# Schematics_-_Remote_Monitoring_Hardware.net
KiCad netlist of a schematic drawn in EAGLE
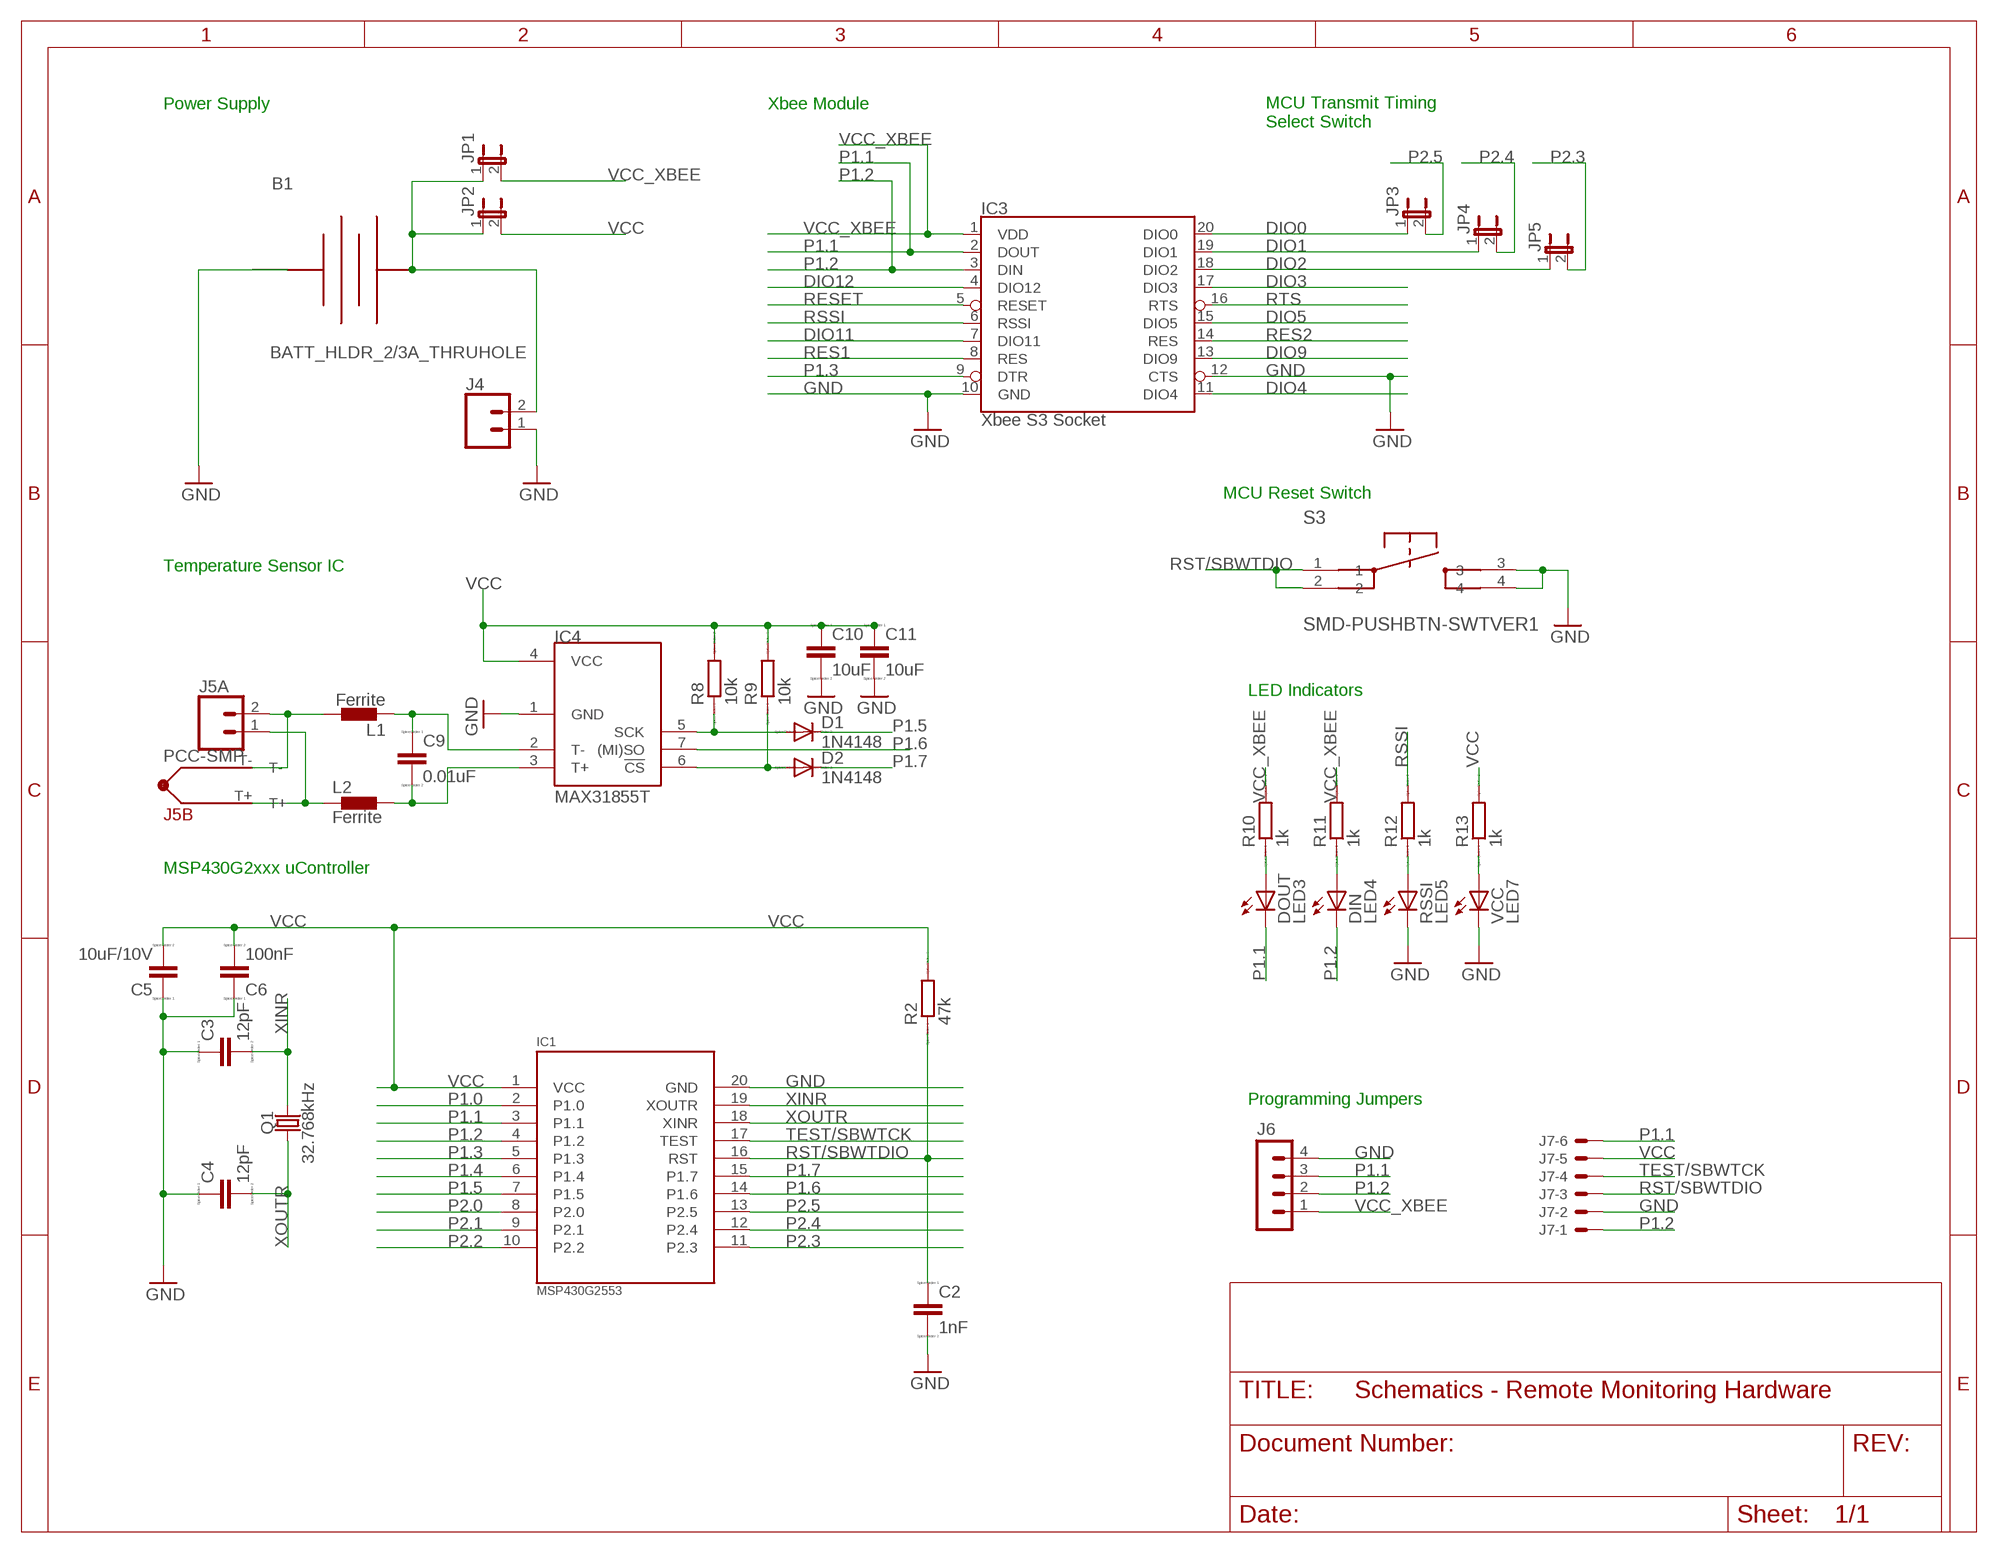
[diagram p0: schematic, sheet 1]

(export (version "E")
  (design (tool "Eeschema 10.0.6"))
  (components
    (comp (ref "B1")
      (value "BATT_HLDR_2/3A_THRUHOLE")
      (footprint "eagle-import:BATT_HLDR_2_3A_THRUHOLE")
      (libsource (lib "eagle-import") (part "BATT_HLDR_2/3A_THRUHOLE"))
    )
    (comp (ref "C2")
      (value "1nF")
      (footprint "eagle-import:C0805")
      (libsource (lib "eagle-import") (part "C"))
    )
    (comp (ref "C3")
      (value "12pF")
      (footprint "eagle-import:C0805")
      (libsource (lib "eagle-import") (part "C"))
    )
    (comp (ref "C4")
      (value "12pF")
      (footprint "eagle-import:C0805")
      (libsource (lib "eagle-import") (part "C"))
    )
    (comp (ref "C5")
      (value "10uF/10V")
      (footprint "eagle-import:C0805")
      (libsource (lib "eagle-import") (part "C"))
    )
    (comp (ref "C6")
      (value "100nF")
      (footprint "eagle-import:C0805")
      (libsource (lib "eagle-import") (part "C"))
    )
    (comp (ref "C9")
      (value "0.01uF")
      (footprint "eagle-import:C0805")
      (libsource (lib "eagle-import") (part "C"))
    )
    (comp (ref "C10")
      (value "10uF")
      (footprint "eagle-import:C0805")
      (libsource (lib "eagle-import") (part "C"))
    )
    (comp (ref "C11")
      (value "10uF")
      (footprint "eagle-import:C0805")
      (libsource (lib "eagle-import") (part "C"))
    )
    (comp (ref "D1")
      (value "1N4148")
      (footprint "eagle-import:SOD323-R")
      (libsource (lib "eagle-import") (part "DIODE-SOD323-R"))
    )
    (comp (ref "D2")
      (value "1N4148")
      (footprint "eagle-import:SOD323-R")
      (libsource (lib "eagle-import") (part "DIODE-SOD323-R"))
    )
    (comp (ref "DIN")
      (value "LED4")
      (footprint "eagle-import:SML0805")
      (libsource (lib "eagle-import") (part "LEDSML0805"))
    )
    (comp (ref "DOUT")
      (value "LED3")
      (footprint "eagle-import:SML0805")
      (libsource (lib "eagle-import") (part "LEDSML0805"))
    )
    (comp (ref "IC1")
      (value "MSP430G2553")
      (footprint "eagle-import:MSP430G2553IPW20")
      (libsource (lib "eagle-import") (part "MSP430G2553IPW20VER2TSSOP-20"))
    )
    (comp (ref "IC3")
      (value "Xbee S3 Socket")
      (footprint "eagle-import:XBEE-LONGPAD")
      (libsource (lib "eagle-import") (part "XBEELONGPAD"))
    )
    (comp (ref "IC4")
      (value "MAX31855T")
      (footprint "eagle-import:SOIC8")
      (libsource (lib "eagle-import") (part "MAX6675"))
    )
    (comp (ref "J4")
      (value "CONN_023.5MM")
      (footprint "eagle-import:SCREWTERMINAL-3.5MM-2")
      (libsource (lib "eagle-import") (part "CONN_023.5MM"))
    )
    (comp (ref "J5A")
      (value "CONN_023.5MM")
      (footprint "eagle-import:SCREWTERMINAL-3.5MM-2")
      (libsource (lib "eagle-import") (part "CONN_023.5MM"))
    )
    (comp (ref "J5B")
      (value "PCC-SMP")
      (footprint "eagle-import:PCC-SMP")
      (libsource (lib "eagle-import") (part "PCC-SMP"))
    )
    (comp (ref "J6")
      (value "MA04-1")
      (footprint "eagle-import:MA04-1")
      (libsource (lib "eagle-import") (part "MA04-1"))
    )
    (comp (ref "J7")
      (value "53047-06")
      (footprint "eagle-import:53047-06")
      (fields (field (name "MPN") "53047-0610-C"))
      (libsource (lib "eagle-import") (part "53?-06047"))
    )
    (comp (ref "JP1")
      (value "JUMPER-2PTH")
      (footprint "eagle-import:1X02")
      (libsource (lib "eagle-import") (part "JUMPER-2PTH"))
    )
    (comp (ref "JP2")
      (value "JUMPER-2PTH")
      (footprint "eagle-import:1X02")
      (libsource (lib "eagle-import") (part "JUMPER-2PTH"))
    )
    (comp (ref "JP3")
      (value "JUMPER-2PTH")
      (footprint "eagle-import:1X02")
      (libsource (lib "eagle-import") (part "JUMPER-2PTH"))
    )
    (comp (ref "JP4")
      (value "JUMPER-2PTH")
      (footprint "eagle-import:1X02")
      (libsource (lib "eagle-import") (part "JUMPER-2PTH"))
    )
    (comp (ref "JP5")
      (value "JUMPER-2PTH")
      (footprint "eagle-import:1X02")
      (libsource (lib "eagle-import") (part "JUMPER-2PTH"))
    )
    (comp (ref "L1")
      (value "Ferrite")
      (footprint "eagle-import:0402")
      (libsource (lib "eagle-import") (part "BLM15HB121SN1"))
    )
    (comp (ref "L2")
      (value "Ferrite")
      (footprint "eagle-import:0402")
      (libsource (lib "eagle-import") (part "BLM15HB121SN1"))
    )
    (comp (ref "Q1")
      (value "32.768kHz")
      (footprint "eagle-import:CRYSTAL-SMD-2X6-CYL")
      (libsource (lib "eagle-import") (part "CRYSTAL-32.768KHZSMD-2X6"))
    )
    (comp (ref "R2")
      (value "47k")
      (footprint "eagle-import:R0805")
      (libsource (lib "eagle-import") (part "R"))
    )
    (comp (ref "R8")
      (value "10k")
      (footprint "eagle-import:R0805")
      (libsource (lib "eagle-import") (part "R"))
    )
    (comp (ref "R9")
      (value "10k")
      (footprint "eagle-import:R0805")
      (libsource (lib "eagle-import") (part "R"))
    )
    (comp (ref "R10")
      (value "1k")
      (footprint "eagle-import:R0805")
      (libsource (lib "eagle-import") (part "R"))
    )
    (comp (ref "R11")
      (value "1k")
      (footprint "eagle-import:R0805")
      (libsource (lib "eagle-import") (part "R"))
    )
    (comp (ref "R12")
      (value "1k")
      (footprint "eagle-import:R0805")
      (libsource (lib "eagle-import") (part "R"))
    )
    (comp (ref "R13")
      (value "1k")
      (footprint "eagle-import:R0805")
      (libsource (lib "eagle-import") (part "R"))
    )
    (comp (ref "RSSI")
      (value "LED5")
      (footprint "eagle-import:SML0805")
      (libsource (lib "eagle-import") (part "LEDSML0805"))
    )
    (comp (ref "S3")
      (value "SMD-PUSHBTN-SWTVER1")
      (footprint "eagle-import:KPT-1187B")
      (libsource (lib "eagle-import") (part "SMD-PUSHBTN-SWTVER1"))
    )
    (comp (ref "VCC")
      (value "LED7")
      (footprint "eagle-import:SML0805")
      (libsource (lib "eagle-import") (part "LEDSML0805"))
    )
  )
  (nets
    (net (code "1") (name "/DIO0") (class "Default")
      (node (ref "IC3") (pin "20") (pinfunction "DIO0_20") (pintype "bidirectional"))
      (node (ref "JP3") (pin "1") (pinfunction "1_1") (pintype "passive"))
    )
    (net (code "2") (name "/DIO1") (class "Default")
      (node (ref "IC3") (pin "19") (pinfunction "DIO1_19") (pintype "bidirectional"))
      (node (ref "JP4") (pin "1") (pinfunction "1_1") (pintype "passive"))
    )
    (net (code "3") (name "/DIO2") (class "Default")
      (node (ref "IC3") (pin "18") (pinfunction "DIO2_18") (pintype "bidirectional"))
      (node (ref "JP5") (pin "1") (pinfunction "1_1") (pintype "passive"))
    )
    (net (code "4") (name "/DIO3") (class "Default")
      (node (ref "IC3") (pin "17") (pinfunction "DIO3_17") (pintype "bidirectional"))
    )
    (net (code "5") (name "/DIO4") (class "Default")
      (node (ref "IC3") (pin "11") (pinfunction "DIO4_11") (pintype "bidirectional"))
    )
    (net (code "6") (name "/DIO5") (class "Default")
      (node (ref "IC3") (pin "15") (pinfunction "DIO5_15") (pintype "bidirectional"))
    )
    (net (code "7") (name "/DIO9") (class "Default")
      (node (ref "IC3") (pin "13") (pinfunction "DIO9_13") (pintype "bidirectional"))
    )
    (net (code "8") (name "/DIO11") (class "Default")
      (node (ref "IC3") (pin "7") (pinfunction "DIO11_7") (pintype "bidirectional"))
    )
    (net (code "9") (name "/DIO12") (class "Default")
      (node (ref "IC3") (pin "4") (pinfunction "DIO12_4") (pintype "bidirectional"))
    )
    (net (code "10") (name "/P1.0") (class "Default")
      (node (ref "IC1") (pin "2") (pinfunction "P1.0_2") (pintype "bidirectional"))
    )
    (net (code "11") (name "/P1.1") (class "Default")
      (node (ref "DOUT") (pin "C") (pinfunction "C_C") (pintype "passive"))
      (node (ref "IC1") (pin "3") (pinfunction "P1.1_3") (pintype "bidirectional"))
      (node (ref "IC3") (pin "2") (pinfunction "DOUT_2") (pintype "output"))
      (node (ref "J6") (pin "3") (pinfunction "3_3") (pintype "passive"))
      (node (ref "J7") (pin "6") (pinfunction "S_6") (pintype "passive"))
    )
    (net (code "12") (name "/P1.2") (class "Default")
      (node (ref "DIN") (pin "C") (pinfunction "C_C") (pintype "passive"))
      (node (ref "IC1") (pin "4") (pinfunction "P1.2_4") (pintype "bidirectional"))
      (node (ref "IC3") (pin "3") (pinfunction "DIN_3") (pintype "input"))
      (node (ref "J6") (pin "2") (pinfunction "2_2") (pintype "passive"))
      (node (ref "J7") (pin "1") (pinfunction "S_1") (pintype "passive"))
    )
    (net (code "13") (name "/P1.3") (class "Default")
      (node (ref "IC1") (pin "5") (pinfunction "P1.3_5") (pintype "bidirectional"))
      (node (ref "IC3") (pin "9") (pinfunction "DTR_9") (pintype "bidirectional"))
    )
    (net (code "14") (name "/P1.4") (class "Default")
      (node (ref "IC1") (pin "6") (pinfunction "P1.4_6") (pintype "bidirectional"))
    )
    (net (code "15") (name "/P1.5") (class "Default")
      (node (ref "D1") (pin "C") (pinfunction "C_C") (pintype "passive"))
      (node (ref "IC1") (pin "7") (pinfunction "P1.5_7") (pintype "bidirectional"))
    )
    (net (code "16") (name "/P1.6") (class "Default")
      (node (ref "IC1") (pin "14") (pinfunction "P1.6_14") (pintype "bidirectional"))
      (node (ref "IC4") (pin "7") (pinfunction "(MI)SO_7") (pintype "bidirectional"))
    )
    (net (code "17") (name "/P1.7") (class "Default")
      (node (ref "D2") (pin "C") (pinfunction "C_C") (pintype "passive"))
      (node (ref "IC1") (pin "15") (pinfunction "P1.7_15") (pintype "bidirectional"))
    )
    (net (code "18") (name "/P2.0") (class "Default")
      (node (ref "IC1") (pin "8") (pinfunction "P2.0_8") (pintype "bidirectional"))
    )
    (net (code "19") (name "/P2.1") (class "Default")
      (node (ref "IC1") (pin "9") (pinfunction "P2.1_9") (pintype "bidirectional"))
    )
    (net (code "20") (name "/P2.2") (class "Default")
      (node (ref "IC1") (pin "10") (pinfunction "P2.2_10") (pintype "bidirectional"))
    )
    (net (code "21") (name "/P2.3") (class "Default")
      (node (ref "IC1") (pin "11") (pinfunction "P2.3_11") (pintype "bidirectional"))
      (node (ref "JP5") (pin "2") (pinfunction "2_2") (pintype "passive"))
    )
    (net (code "22") (name "/P2.4") (class "Default")
      (node (ref "IC1") (pin "12") (pinfunction "P2.4_12") (pintype "bidirectional"))
      (node (ref "JP4") (pin "2") (pinfunction "2_2") (pintype "passive"))
    )
    (net (code "23") (name "/P2.5") (class "Default")
      (node (ref "IC1") (pin "13") (pinfunction "P2.5_13") (pintype "bidirectional"))
      (node (ref "JP3") (pin "2") (pinfunction "2_2") (pintype "passive"))
    )
    (net (code "24") (name "/RES1") (class "Default")
      (node (ref "IC3") (pin "8") (pinfunction "RES_8") (pintype "bidirectional"))
    )
    (net (code "25") (name "/RES2") (class "Default")
      (node (ref "IC3") (pin "14") (pinfunction "RES_14") (pintype "bidirectional"))
    )
    (net (code "26") (name "/RESET") (class "Default")
      (node (ref "IC3") (pin "5") (pinfunction "RESET_5") (pintype "input"))
    )
    (net (code "27") (name "/RSSI") (class "Default")
      (node (ref "IC3") (pin "6") (pinfunction "RSSI_6") (pintype "bidirectional"))
      (node (ref "R12") (pin "2") (pinfunction "2_2") (pintype "passive"))
    )
    (net (code "28") (name "/RST{slash}SBWTDIO") (class "Default")
      (node (ref "C2") (pin "1") (pinfunction "1_1") (pintype "passive"))
      (node (ref "IC1") (pin "16") (pinfunction "RST_16") (pintype "bidirectional"))
      (node (ref "J7") (pin "3") (pinfunction "S_3") (pintype "passive"))
      (node (ref "R2") (pin "1") (pinfunction "1_1") (pintype "passive"))
      (node (ref "S3") (pin "1") (pinfunction "1_1") (pintype "bidirectional"))
      (node (ref "S3") (pin "2") (pinfunction "2_2") (pintype "bidirectional"))
    )
    (net (code "29") (name "/RTS") (class "Default")
      (node (ref "IC3") (pin "16") (pinfunction "RTS_16") (pintype "input"))
    )
    (net (code "30") (name "/TEST{slash}SBWTCK") (class "Default")
      (node (ref "IC1") (pin "17") (pinfunction "TEST_17") (pintype "bidirectional"))
      (node (ref "J7") (pin "4") (pinfunction "S_4") (pintype "passive"))
    )
    (net (code "31") (name "/VCC") (class "Default")
      (node (ref "C10") (pin "1") (pinfunction "1_1") (pintype "passive"))
      (node (ref "C11") (pin "1") (pinfunction "1_1") (pintype "passive"))
      (node (ref "C5") (pin "2") (pinfunction "2_2") (pintype "passive"))
      (node (ref "C6") (pin "2") (pinfunction "2_2") (pintype "passive"))
      (node (ref "IC1") (pin "1") (pinfunction "VCC_1") (pintype "power_in"))
      (node (ref "IC4") (pin "4") (pinfunction "VCC_4") (pintype "bidirectional"))
      (node (ref "J7") (pin "5") (pinfunction "S_5") (pintype "passive"))
      (node (ref "JP2") (pin "2") (pinfunction "2_2") (pintype "passive"))
      (node (ref "R13") (pin "2") (pinfunction "2_2") (pintype "passive"))
      (node (ref "R2") (pin "2") (pinfunction "2_2") (pintype "passive"))
      (node (ref "R8") (pin "2") (pinfunction "2_2") (pintype "passive"))
      (node (ref "R9") (pin "2") (pinfunction "2_2") (pintype "passive"))
    )
    (net (code "32") (name "/VCC_XBEE") (class "Default")
      (node (ref "IC3") (pin "1") (pinfunction "VDD_1") (pintype "power_in"))
      (node (ref "J6") (pin "1") (pinfunction "1_1") (pintype "passive"))
      (node (ref "JP1") (pin "2") (pinfunction "2_2") (pintype "passive"))
      (node (ref "R10") (pin "2") (pinfunction "2_2") (pintype "passive"))
      (node (ref "R11") (pin "2") (pinfunction "2_2") (pintype "passive"))
    )
    (net (code "33") (name "/XINR") (class "Default")
      (node (ref "C3") (pin "2") (pinfunction "2_2") (pintype "passive"))
      (node (ref "IC1") (pin "19") (pinfunction "XOUTR_19") (pintype "bidirectional"))
      (node (ref "Q1") (pin "X2") (pinfunction "2_X2") (pintype "passive"))
    )
    (net (code "34") (name "/XOUTR") (class "Default")
      (node (ref "C4") (pin "2") (pinfunction "2_2") (pintype "passive"))
      (node (ref "IC1") (pin "18") (pinfunction "XINR_18") (pintype "bidirectional"))
      (node (ref "Q1") (pin "X1") (pinfunction "1_X1") (pintype "passive"))
    )
    (net (code "35") (name "GND") (class "Default")
      (node (ref "B1") (pin "NEG") (pinfunction "NEG_NEG") (pintype "power_in"))
      (node (ref "C10") (pin "2") (pinfunction "2_2") (pintype "passive"))
      (node (ref "C11") (pin "2") (pinfunction "2_2") (pintype "passive"))
      (node (ref "C2") (pin "2") (pinfunction "2_2") (pintype "passive"))
      (node (ref "C3") (pin "1") (pinfunction "1_1") (pintype "passive"))
      (node (ref "C4") (pin "1") (pinfunction "1_1") (pintype "passive"))
      (node (ref "C5") (pin "1") (pinfunction "1_1") (pintype "passive"))
      (node (ref "C6") (pin "1") (pinfunction "1_1") (pintype "passive"))
      (node (ref "IC1") (pin "20") (pinfunction "GND_20") (pintype "power_in"))
      (node (ref "IC3") (pin "10") (pinfunction "GND_10") (pintype "power_in"))
      (node (ref "IC3") (pin "12") (pinfunction "CTS_12") (pintype "output"))
      (node (ref "IC4") (pin "1") (pinfunction "GND_1") (pintype "bidirectional"))
      (node (ref "J4") (pin "1") (pinfunction "1_1") (pintype "passive"))
      (node (ref "J6") (pin "4") (pinfunction "4_4") (pintype "passive"))
      (node (ref "J7") (pin "2") (pinfunction "S_2") (pintype "passive"))
      (node (ref "RSSI") (pin "C") (pinfunction "C_C") (pintype "passive"))
      (node (ref "S3") (pin "3") (pinfunction "3_3") (pintype "bidirectional"))
      (node (ref "S3") (pin "4") (pinfunction "4_4") (pintype "bidirectional"))
      (node (ref "VCC") (pin "C") (pinfunction "C_C") (pintype "passive"))
    )
    (net (code "36") (name "Net-(B1-PadPOS)") (class "Default")
      (node (ref "B1") (pin "POS") (pinfunction "POS_POS") (pintype "power_in"))
      (node (ref "J4") (pin "2") (pinfunction "2_2") (pintype "passive"))
      (node (ref "JP1") (pin "1") (pinfunction "1_1") (pintype "passive"))
      (node (ref "JP2") (pin "1") (pinfunction "1_1") (pintype "passive"))
    )
    (net (code "37") (name "Net-(DIN-PadA)") (class "Default")
      (node (ref "DIN") (pin "A") (pinfunction "A_A") (pintype "passive"))
      (node (ref "R11") (pin "1") (pinfunction "1_1") (pintype "passive"))
    )
    (net (code "38") (name "Net-(DOUT-PadA)") (class "Default")
      (node (ref "DOUT") (pin "A") (pinfunction "A_A") (pintype "passive"))
      (node (ref "R10") (pin "1") (pinfunction "1_1") (pintype "passive"))
    )
    (net (code "39") (name "Net-(IC4-SCK)") (class "Default")
      (node (ref "D1") (pin "A") (pinfunction "A_A") (pintype "passive"))
      (node (ref "IC4") (pin "5") (pinfunction "SCK_5") (pintype "bidirectional"))
      (node (ref "R8") (pin "1") (pinfunction "1_1") (pintype "passive"))
    )
    (net (code "40") (name "Net-(IC4-T+)") (class "Default")
      (node (ref "C9") (pin "2") (pinfunction "2_2") (pintype "passive"))
      (node (ref "IC4") (pin "3") (pinfunction "T+_3") (pintype "bidirectional"))
      (node (ref "L2") (pin "2") (pinfunction "2_2") (pintype "passive"))
    )
    (net (code "41") (name "Net-(IC4-T-)") (class "Default")
      (node (ref "C9") (pin "1") (pinfunction "1_1") (pintype "passive"))
      (node (ref "IC4") (pin "2") (pinfunction "T-_2") (pintype "bidirectional"))
      (node (ref "L1") (pin "1") (pinfunction "1_1") (pintype "passive"))
    )
    (net (code "42") (name "Net-(IC4-~{CS})") (class "Default")
      (node (ref "D2") (pin "A") (pinfunction "A_A") (pintype "passive"))
      (node (ref "IC4") (pin "6") (pinfunction "~{CS}_6") (pintype "bidirectional"))
      (node (ref "R9") (pin "1") (pinfunction "1_1") (pintype "passive"))
    )
    (net (code "43") (name "Net-(J5A-Pad1)") (class "Default")
      (node (ref "J5A") (pin "1") (pinfunction "1_1") (pintype "passive"))
      (node (ref "J5B") (pin "T+") (pinfunction "T+_T+") (pintype "bidirectional"))
      (node (ref "L2") (pin "1") (pinfunction "1_1") (pintype "passive"))
    )
    (net (code "44") (name "Net-(J5A-Pad2)") (class "Default")
      (node (ref "J5A") (pin "2") (pinfunction "2_2") (pintype "passive"))
      (node (ref "J5B") (pin "T-") (pinfunction "T-_T-") (pintype "bidirectional"))
      (node (ref "L1") (pin "2") (pinfunction "2_2") (pintype "passive"))
    )
    (net (code "45") (name "Net-(R12-Pad1)") (class "Default")
      (node (ref "R12") (pin "1") (pinfunction "1_1") (pintype "passive"))
      (node (ref "RSSI") (pin "A") (pinfunction "A_A") (pintype "passive"))
    )
    (net (code "46") (name "Net-(R13-Pad1)") (class "Default")
      (node (ref "R13") (pin "1") (pinfunction "1_1") (pintype "passive"))
      (node (ref "VCC") (pin "A") (pinfunction "A_A") (pintype "passive"))
    )
  )
)
